# revA.net
KiCad netlist of a schematic drawn in EAGLE
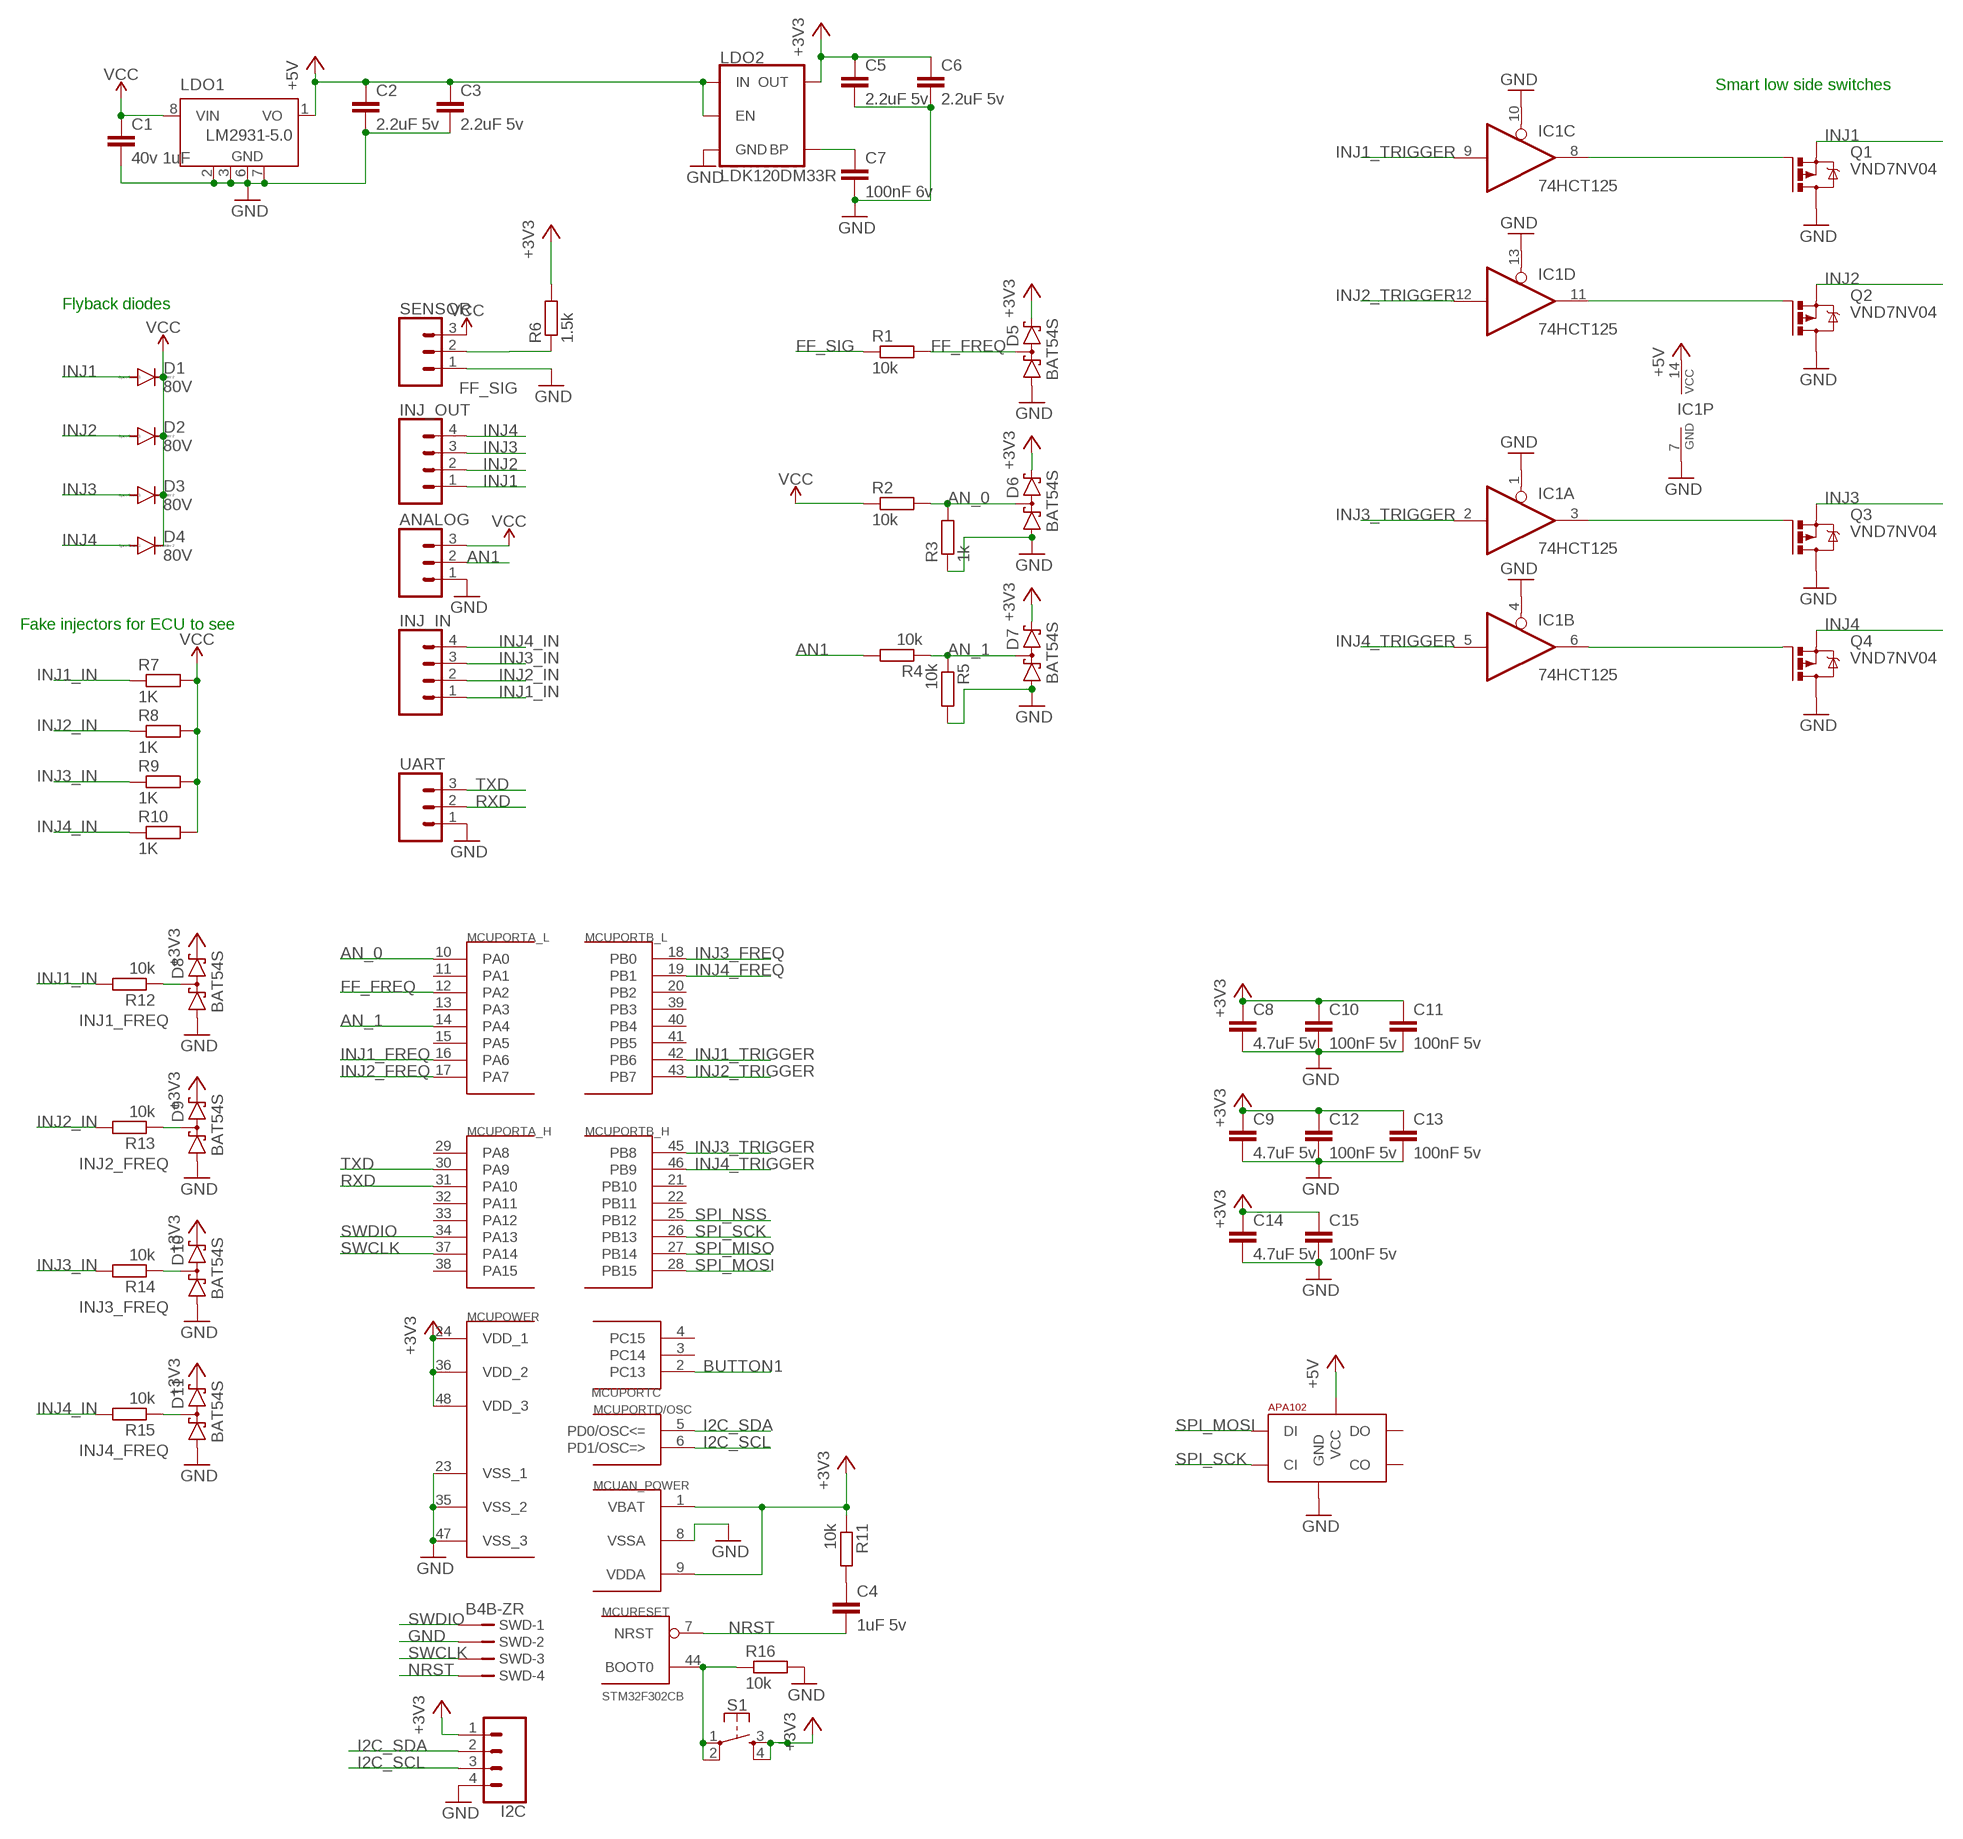
[diagram p0: schematic, sheet 1]

(export (version "E")
  (design (tool "Eeschema 10.0.6"))
  (components
    (comp (ref "ANALOG")
      (value "CONN_03POLAR_LOCK")
      (footprint "eagle-import:MOLEX-1X3_LOCK")
      (libsource (lib "eagle-import") (part "CONN_03POLAR_LOCK"))
    )
    (comp (ref "C1")
      (value "40v 1uF")
      (footprint "eagle-import:C0603")
      (libsource (lib "eagle-import") (part "C-EUC0603"))
    )
    (comp (ref "C2")
      (value "2.2uF 5v")
      (footprint "eagle-import:C0603")
      (libsource (lib "eagle-import") (part "C-EUC0603"))
    )
    (comp (ref "C3")
      (value "2.2uF 5v")
      (footprint "eagle-import:C0603")
      (libsource (lib "eagle-import") (part "C-EUC0603"))
    )
    (comp (ref "C4")
      (value "1uF 5v")
      (footprint "eagle-import:C0603")
      (libsource (lib "eagle-import") (part "C-EUC0603"))
    )
    (comp (ref "C5")
      (value "2.2uF 5v")
      (footprint "eagle-import:C0603")
      (libsource (lib "eagle-import") (part "C-EUC0603"))
    )
    (comp (ref "C6")
      (value "2.2uF 5v")
      (footprint "eagle-import:C0603")
      (libsource (lib "eagle-import") (part "C-EUC0603"))
    )
    (comp (ref "C7")
      (value "100nF 6v")
      (footprint "eagle-import:C0603")
      (libsource (lib "eagle-import") (part "C-EUC0603"))
    )
    (comp (ref "C8")
      (value "4.7uF 5v")
      (footprint "eagle-import:C0603")
      (libsource (lib "eagle-import") (part "C-EUC0603"))
    )
    (comp (ref "C9")
      (value "4.7uF 5v")
      (footprint "eagle-import:C0603")
      (libsource (lib "eagle-import") (part "C-EUC0603"))
    )
    (comp (ref "C10")
      (value "100nF 5v")
      (footprint "eagle-import:C0603")
      (libsource (lib "eagle-import") (part "C-EUC0603"))
    )
    (comp (ref "C11")
      (value "100nF 5v")
      (footprint "eagle-import:C0603")
      (libsource (lib "eagle-import") (part "C-EUC0603"))
    )
    (comp (ref "C12")
      (value "100nF 5v")
      (footprint "eagle-import:C0603")
      (libsource (lib "eagle-import") (part "C-EUC0603"))
    )
    (comp (ref "C13")
      (value "100nF 5v")
      (footprint "eagle-import:C0603")
      (libsource (lib "eagle-import") (part "C-EUC0603"))
    )
    (comp (ref "C14")
      (value "4.7uF 5v")
      (footprint "eagle-import:C0603")
      (libsource (lib "eagle-import") (part "C-EUC0603"))
    )
    (comp (ref "C15")
      (value "100nF 5v")
      (footprint "eagle-import:C0603")
      (libsource (lib "eagle-import") (part "C-EUC0603"))
    )
    (comp (ref "D1")
      (value "80V")
      (footprint "eagle-import:SMB")
      (libsource (lib "eagle-import") (part "DIODE-SMB"))
    )
    (comp (ref "D2")
      (value "80V")
      (footprint "eagle-import:SMB")
      (libsource (lib "eagle-import") (part "DIODE-SMB"))
    )
    (comp (ref "D3")
      (value "80V")
      (footprint "eagle-import:SMB")
      (libsource (lib "eagle-import") (part "DIODE-SMB"))
    )
    (comp (ref "D4")
      (value "80V")
      (footprint "eagle-import:SMB")
      (libsource (lib "eagle-import") (part "DIODE-SMB"))
    )
    (comp (ref "D5")
      (value "BAT54S")
      (footprint "eagle-import:SOT23")
      (libsource (lib "eagle-import") (part "BAT54S"))
    )
    (comp (ref "D6")
      (value "BAT54S")
      (footprint "eagle-import:SOT23")
      (libsource (lib "eagle-import") (part "BAT54S"))
    )
    (comp (ref "D7")
      (value "BAT54S")
      (footprint "eagle-import:SOT23")
      (libsource (lib "eagle-import") (part "BAT54S"))
    )
    (comp (ref "D8")
      (value "BAT54S")
      (footprint "eagle-import:SOT23")
      (libsource (lib "eagle-import") (part "BAT54S"))
    )
    (comp (ref "D9")
      (value "BAT54S")
      (footprint "eagle-import:SOT23")
      (libsource (lib "eagle-import") (part "BAT54S"))
    )
    (comp (ref "D10")
      (value "BAT54S")
      (footprint "eagle-import:SOT23")
      (libsource (lib "eagle-import") (part "BAT54S"))
    )
    (comp (ref "D11")
      (value "BAT54S")
      (footprint "eagle-import:SOT23")
      (libsource (lib "eagle-import") (part "BAT54S"))
    )
    (comp (ref "I2C")
      (value "CONN_04POLAR_LOCK")
      (footprint "eagle-import:MOLEX-1X4_LOCK")
      (libsource (lib "eagle-import") (part "CONN_04POLAR_LOCK"))
    )
    (comp (ref "IC1")
      (value "74HCT125")
      (footprint "eagle-import:TSSOP14")
      (libsource (lib "eagle-import") (part "74125PWABT"))
    )
    (comp (ref "INJ_IN")
      (value "CONN_04POLAR_LOCK")
      (footprint "eagle-import:MOLEX-1X4_LOCK")
      (libsource (lib "eagle-import") (part "CONN_04POLAR_LOCK"))
    )
    (comp (ref "INJ_OUT")
      (value "CONN_04POLAR_LOCK")
      (footprint "eagle-import:MOLEX-1X4_LOCK")
      (libsource (lib "eagle-import") (part "CONN_04POLAR_LOCK"))
    )
    (comp (ref "LDO1")
      (value "LM2931-5.0")
      (footprint "eagle-import:SO08")
      (fields (field (name "MF") "NATIONAL SEMICONDUCTOR") (field (name "MPN") "LM2936M-5.0/NOPB"))
      (libsource (lib "eagle-import") (part "LM2936M?-5.0"))
    )
    (comp (ref "LDO2")
      (value "LDK120DM33R")
      (footprint "eagle-import:SOT23-5")
      (libsource (lib "eagle-import") (part "V_REG_MIC52053.3V"))
    )
    (comp (ref "LED")
      (value "APA1025050")
      (footprint "eagle-import:APA102_5050")
      (libsource (lib "eagle-import") (part "APA1025050"))
    )
    (comp (ref "MCU")
      (value "STM32F302CB")
      (footprint "eagle-import:LQFP48_2")
      (libsource (lib "eagle-import") (part "STM32F10XCXT6"))
    )
    (comp (ref "Q1")
      (value "VND7NV04")
      (footprint "eagle-import:D-PAK_TO252AA")
      (libsource (lib "eagle-import") (part "IRF?5305R"))
    )
    (comp (ref "Q2")
      (value "VND7NV04")
      (footprint "eagle-import:D-PAK_TO252AA")
      (libsource (lib "eagle-import") (part "IRF?5305R"))
    )
    (comp (ref "Q3")
      (value "VND7NV04")
      (footprint "eagle-import:D-PAK_TO252AA")
      (libsource (lib "eagle-import") (part "IRF?5305R"))
    )
    (comp (ref "Q4")
      (value "VND7NV04")
      (footprint "eagle-import:D-PAK_TO252AA")
      (libsource (lib "eagle-import") (part "IRF?5305R"))
    )
    (comp (ref "R1")
      (value "10k")
      (footprint "eagle-import:R0603")
      (libsource (lib "eagle-import") (part "R-EU_R0603"))
    )
    (comp (ref "R2")
      (value "10k")
      (footprint "eagle-import:R0603")
      (libsource (lib "eagle-import") (part "R-EU_R0603"))
    )
    (comp (ref "R3")
      (value "1k")
      (footprint "eagle-import:R0603")
      (libsource (lib "eagle-import") (part "R-EU_R0603"))
    )
    (comp (ref "R4")
      (value "10k")
      (footprint "eagle-import:R0603")
      (libsource (lib "eagle-import") (part "R-EU_R0603"))
    )
    (comp (ref "R5")
      (value "10k")
      (footprint "eagle-import:R0603")
      (libsource (lib "eagle-import") (part "R-EU_R0603"))
    )
    (comp (ref "R6")
      (value "1.5k")
      (footprint "eagle-import:R0603")
      (libsource (lib "eagle-import") (part "R-EU_R0603"))
    )
    (comp (ref "R7")
      (value "1K")
      (footprint "eagle-import:0414_15")
      (libsource (lib "eagle-import") (part "R-EU_0414/15"))
    )
    (comp (ref "R8")
      (value "1K")
      (footprint "eagle-import:0414_15")
      (libsource (lib "eagle-import") (part "R-EU_0414/15"))
    )
    (comp (ref "R9")
      (value "1K")
      (footprint "eagle-import:0414_15")
      (libsource (lib "eagle-import") (part "R-EU_0414/15"))
    )
    (comp (ref "R10")
      (value "1K")
      (footprint "eagle-import:0414_15")
      (libsource (lib "eagle-import") (part "R-EU_0414/15"))
    )
    (comp (ref "R11")
      (value "10k")
      (footprint "eagle-import:R0603")
      (libsource (lib "eagle-import") (part "R-EU_R0603"))
    )
    (comp (ref "R12")
      (value "10k")
      (footprint "eagle-import:R0603")
      (libsource (lib "eagle-import") (part "R-EU_R0603"))
    )
    (comp (ref "R13")
      (value "10k")
      (footprint "eagle-import:R0603")
      (libsource (lib "eagle-import") (part "R-EU_R0603"))
    )
    (comp (ref "R14")
      (value "10k")
      (footprint "eagle-import:R0603")
      (libsource (lib "eagle-import") (part "R-EU_R0603"))
    )
    (comp (ref "R15")
      (value "10k")
      (footprint "eagle-import:R0603")
      (libsource (lib "eagle-import") (part "R-EU_R0603"))
    )
    (comp (ref "R16")
      (value "10k")
      (footprint "eagle-import:R0603")
      (libsource (lib "eagle-import") (part "R-EU_R0603"))
    )
    (comp (ref "S1")
      (value "MOMENTARY-SWITCH-SPST-2-SMD-5.2MM")
      (footprint "eagle-import:TACTILE_SWITCH_SMD_5.2MM")
      (libsource (lib "eagle-import") (part "MOMENTARY-SWITCH-SPST-2-SMD-5.2MM"))
    )
    (comp (ref "SENSOR")
      (value "CONN_03POLAR_LOCK")
      (footprint "eagle-import:MOLEX-1X3_LOCK")
      (libsource (lib "eagle-import") (part "CONN_03POLAR_LOCK"))
    )
    (comp (ref "SWD")
      (value "B4B-ZR")
      (footprint "eagle-import:B4B-ZR")
      (fields (field (name "MF") "FARNELL") (field (name "MPN") "B4B-ZR(LF)(SN)"))
      (libsource (lib "eagle-import") (part "?4B-ZRB"))
    )
    (comp (ref "UART")
      (value "CONN_03POLAR_LOCK")
      (footprint "eagle-import:MOLEX-1X3_LOCK")
      (libsource (lib "eagle-import") (part "CONN_03POLAR_LOCK"))
    )
  )
  (nets
    (net (code "1") (name "+3V3") (class "Default")
      (node (ref "C10") (pin "1") (pinfunction "1_1") (pintype "passive"))
      (node (ref "C11") (pin "1") (pinfunction "1_1") (pintype "passive"))
      (node (ref "C12") (pin "1") (pinfunction "1_1") (pintype "passive"))
      (node (ref "C13") (pin "1") (pinfunction "1_1") (pintype "passive"))
      (node (ref "C14") (pin "1") (pinfunction "1_1") (pintype "passive"))
      (node (ref "C15") (pin "1") (pinfunction "1_1") (pintype "passive"))
      (node (ref "C5") (pin "1") (pinfunction "1_1") (pintype "passive"))
      (node (ref "C6") (pin "1") (pinfunction "1_1") (pintype "passive"))
      (node (ref "C8") (pin "1") (pinfunction "1_1") (pintype "passive"))
      (node (ref "C9") (pin "1") (pinfunction "1_1") (pintype "passive"))
      (node (ref "D10") (pin "2") (pinfunction "C2_2") (pintype "passive"))
      (node (ref "D11") (pin "2") (pinfunction "C2_2") (pintype "passive"))
      (node (ref "D5") (pin "2") (pinfunction "C2_2") (pintype "passive"))
      (node (ref "D6") (pin "2") (pinfunction "C2_2") (pintype "passive"))
      (node (ref "D7") (pin "2") (pinfunction "C2_2") (pintype "passive"))
      (node (ref "D8") (pin "2") (pinfunction "C2_2") (pintype "passive"))
      (node (ref "D9") (pin "2") (pinfunction "C2_2") (pintype "passive"))
      (node (ref "I2C") (pin "1") (pinfunction "1_1") (pintype "passive"))
      (node (ref "LDO2") (pin "5") (pinfunction "OUT_5") (pintype "passive"))
      (node (ref "MCU") (pin "1") (pinfunction "VBAT_1") (pintype "power_in"))
      (node (ref "MCU") (pin "24") (pinfunction "VDD_1_24") (pintype "power_in"))
      (node (ref "MCU") (pin "36") (pinfunction "VDD_2_36") (pintype "power_in"))
      (node (ref "MCU") (pin "48") (pinfunction "VDD_3_48") (pintype "power_in"))
      (node (ref "MCU") (pin "9") (pinfunction "VDDA_9") (pintype "power_in"))
      (node (ref "R11") (pin "1") (pinfunction "1_1") (pintype "passive"))
      (node (ref "R6") (pin "2") (pinfunction "2_2") (pintype "passive"))
      (node (ref "S1") (pin "3") (pinfunction "3_3") (pintype "passive"))
      (node (ref "S1") (pin "4") (pinfunction "4_4") (pintype "passive"))
    )
    (net (code "2") (name "+5V") (class "Default")
      (node (ref "C2") (pin "1") (pinfunction "1_1") (pintype "passive"))
      (node (ref "C3") (pin "1") (pinfunction "1_1") (pintype "passive"))
      (node (ref "IC1") (pin "14") (pinfunction "VCC_14") (pintype "power_in"))
      (node (ref "LDO1") (pin "1") (pinfunction "VO_1") (pintype "passive"))
      (node (ref "LDO2") (pin "1") (pinfunction "IN_1") (pintype "input"))
      (node (ref "LDO2") (pin "3") (pinfunction "EN_3") (pintype "input"))
      (node (ref "LED") (pin "1") (pinfunction "VCC_1") (pintype "bidirectional"))
    )
    (net (code "3") (name "/AN1") (class "Default")
      (node (ref "ANALOG") (pin "2") (pinfunction "2_2") (pintype "passive"))
      (node (ref "R4") (pin "2") (pinfunction "2_2") (pintype "passive"))
    )
    (net (code "4") (name "/AN_0") (class "Default")
      (node (ref "D6") (pin "3") (pinfunction "C1A2_3") (pintype "passive"))
      (node (ref "MCU") (pin "10") (pinfunction "PA0_10") (pintype "bidirectional"))
      (node (ref "R2") (pin "2") (pinfunction "2_2") (pintype "passive"))
      (node (ref "R3") (pin "2") (pinfunction "2_2") (pintype "passive"))
    )
    (net (code "5") (name "/AN_1") (class "Default")
      (node (ref "D7") (pin "3") (pinfunction "C1A2_3") (pintype "passive"))
      (node (ref "MCU") (pin "14") (pinfunction "PA4_14") (pintype "bidirectional"))
      (node (ref "R4") (pin "1") (pinfunction "1_1") (pintype "passive"))
      (node (ref "R5") (pin "1") (pinfunction "1_1") (pintype "passive"))
    )
    (net (code "6") (name "/BUTTON1") (class "Default")
      (node (ref "MCU") (pin "2") (pinfunction "PC13_2") (pintype "bidirectional"))
    )
    (net (code "7") (name "/FF_FREQ") (class "Default")
      (node (ref "D5") (pin "3") (pinfunction "C1A2_3") (pintype "passive"))
      (node (ref "MCU") (pin "12") (pinfunction "PA2_12") (pintype "bidirectional"))
      (node (ref "R1") (pin "2") (pinfunction "2_2") (pintype "passive"))
    )
    (net (code "8") (name "/FF_SIG") (class "Default")
      (node (ref "R1") (pin "1") (pinfunction "1_1") (pintype "passive"))
      (node (ref "R6") (pin "1") (pinfunction "1_1") (pintype "passive"))
      (node (ref "SENSOR") (pin "2") (pinfunction "2_2") (pintype "passive"))
    )
    (net (code "9") (name "/I2C_SCL") (class "Default")
      (node (ref "I2C") (pin "3") (pinfunction "3_3") (pintype "passive"))
      (node (ref "MCU") (pin "6") (pinfunction "PD1/OSC=>_6") (pintype "bidirectional"))
    )
    (net (code "10") (name "/I2C_SDA") (class "Default")
      (node (ref "I2C") (pin "2") (pinfunction "2_2") (pintype "passive"))
      (node (ref "MCU") (pin "5") (pinfunction "PD0/OSC<=_5") (pintype "bidirectional"))
    )
    (net (code "11") (name "/INJ1") (class "Default")
      (node (ref "D1") (pin "A") (pinfunction "A_A") (pintype "passive"))
      (node (ref "INJ_OUT") (pin "1") (pinfunction "1_1") (pintype "passive"))
      (node (ref "Q1") (pin "3") (pinfunction "S_3") (pintype "passive"))
    )
    (net (code "12") (name "/INJ1_FREQ") (class "Default")
      (node (ref "D8") (pin "3") (pinfunction "C1A2_3") (pintype "passive"))
      (node (ref "MCU") (pin "16") (pinfunction "PA6_16") (pintype "bidirectional"))
      (node (ref "R12") (pin "1") (pinfunction "1_1") (pintype "passive"))
    )
    (net (code "13") (name "/INJ1_IN") (class "Default")
      (node (ref "INJ_IN") (pin "1") (pinfunction "1_1") (pintype "passive"))
      (node (ref "R12") (pin "2") (pinfunction "2_2") (pintype "passive"))
      (node (ref "R7") (pin "1") (pinfunction "1_1") (pintype "passive"))
    )
    (net (code "14") (name "/INJ1_TRIGGER") (class "Default")
      (node (ref "IC1") (pin "9") (pinfunction "I_9") (pintype "input"))
      (node (ref "MCU") (pin "42") (pinfunction "PB6_42") (pintype "bidirectional"))
    )
    (net (code "15") (name "/INJ2") (class "Default")
      (node (ref "D2") (pin "A") (pinfunction "A_A") (pintype "passive"))
      (node (ref "INJ_OUT") (pin "2") (pinfunction "2_2") (pintype "passive"))
      (node (ref "Q2") (pin "3") (pinfunction "S_3") (pintype "passive"))
    )
    (net (code "16") (name "/INJ2_FREQ") (class "Default")
      (node (ref "D9") (pin "3") (pinfunction "C1A2_3") (pintype "passive"))
      (node (ref "MCU") (pin "17") (pinfunction "PA7_17") (pintype "bidirectional"))
      (node (ref "R13") (pin "1") (pinfunction "1_1") (pintype "passive"))
    )
    (net (code "17") (name "/INJ2_IN") (class "Default")
      (node (ref "INJ_IN") (pin "2") (pinfunction "2_2") (pintype "passive"))
      (node (ref "R13") (pin "2") (pinfunction "2_2") (pintype "passive"))
      (node (ref "R8") (pin "1") (pinfunction "1_1") (pintype "passive"))
    )
    (net (code "18") (name "/INJ2_TRIGGER") (class "Default")
      (node (ref "IC1") (pin "12") (pinfunction "I_12") (pintype "input"))
      (node (ref "MCU") (pin "43") (pinfunction "PB7_43") (pintype "bidirectional"))
    )
    (net (code "19") (name "/INJ3") (class "Default")
      (node (ref "D3") (pin "A") (pinfunction "A_A") (pintype "passive"))
      (node (ref "INJ_OUT") (pin "3") (pinfunction "3_3") (pintype "passive"))
      (node (ref "Q3") (pin "3") (pinfunction "S_3") (pintype "passive"))
    )
    (net (code "20") (name "/INJ3_FREQ") (class "Default")
      (node (ref "D10") (pin "3") (pinfunction "C1A2_3") (pintype "passive"))
      (node (ref "MCU") (pin "18") (pinfunction "PB0_18") (pintype "bidirectional"))
      (node (ref "R14") (pin "1") (pinfunction "1_1") (pintype "passive"))
    )
    (net (code "21") (name "/INJ3_IN") (class "Default")
      (node (ref "INJ_IN") (pin "3") (pinfunction "3_3") (pintype "passive"))
      (node (ref "R14") (pin "2") (pinfunction "2_2") (pintype "passive"))
      (node (ref "R9") (pin "1") (pinfunction "1_1") (pintype "passive"))
    )
    (net (code "22") (name "/INJ3_TRIGGER") (class "Default")
      (node (ref "IC1") (pin "2") (pinfunction "I_2") (pintype "input"))
      (node (ref "MCU") (pin "45") (pinfunction "PB8_45") (pintype "bidirectional"))
    )
    (net (code "23") (name "/INJ4") (class "Default")
      (node (ref "D4") (pin "A") (pinfunction "A_A") (pintype "passive"))
      (node (ref "INJ_OUT") (pin "4") (pinfunction "4_4") (pintype "passive"))
      (node (ref "Q4") (pin "3") (pinfunction "S_3") (pintype "passive"))
    )
    (net (code "24") (name "/INJ4_FREQ") (class "Default")
      (node (ref "D11") (pin "3") (pinfunction "C1A2_3") (pintype "passive"))
      (node (ref "MCU") (pin "19") (pinfunction "PB1_19") (pintype "bidirectional"))
      (node (ref "R15") (pin "1") (pinfunction "1_1") (pintype "passive"))
    )
    (net (code "25") (name "/INJ4_IN") (class "Default")
      (node (ref "INJ_IN") (pin "4") (pinfunction "4_4") (pintype "passive"))
      (node (ref "R10") (pin "1") (pinfunction "1_1") (pintype "passive"))
      (node (ref "R15") (pin "2") (pinfunction "2_2") (pintype "passive"))
    )
    (net (code "26") (name "/INJ4_TRIGGER") (class "Default")
      (node (ref "IC1") (pin "5") (pinfunction "I_5") (pintype "input"))
      (node (ref "MCU") (pin "46") (pinfunction "PB9_46") (pintype "bidirectional"))
    )
    (net (code "27") (name "/NRST") (class "Default")
      (node (ref "C4") (pin "2") (pinfunction "2_2") (pintype "passive"))
      (node (ref "MCU") (pin "7") (pinfunction "NRST_7") (pintype "input"))
      (node (ref "SWD") (pin "4") (pinfunction "1_4") (pintype "passive"))
    )
    (net (code "28") (name "/RXD") (class "Default")
      (node (ref "MCU") (pin "31") (pinfunction "PA10_31") (pintype "bidirectional"))
      (node (ref "UART") (pin "2") (pinfunction "2_2") (pintype "passive"))
    )
    (net (code "29") (name "/SPI_MISO") (class "Default")
      (node (ref "MCU") (pin "27") (pinfunction "PB14_27") (pintype "bidirectional"))
    )
    (net (code "30") (name "/SPI_MOSI") (class "Default")
      (node (ref "LED") (pin "4") (pinfunction "DI_4") (pintype "bidirectional"))
      (node (ref "MCU") (pin "28") (pinfunction "PB15_28") (pintype "bidirectional"))
    )
    (net (code "31") (name "/SPI_NSS") (class "Default")
      (node (ref "MCU") (pin "25") (pinfunction "PB12_25") (pintype "bidirectional"))
    )
    (net (code "32") (name "/SPI_SCK") (class "Default")
      (node (ref "LED") (pin "5") (pinfunction "CI_5") (pintype "bidirectional"))
      (node (ref "MCU") (pin "26") (pinfunction "PB13_26") (pintype "bidirectional"))
    )
    (net (code "33") (name "/SWCLK") (class "Default")
      (node (ref "MCU") (pin "37") (pinfunction "PA14_37") (pintype "bidirectional"))
      (node (ref "SWD") (pin "3") (pinfunction "1_3") (pintype "passive"))
    )
    (net (code "34") (name "/SWDIO") (class "Default")
      (node (ref "MCU") (pin "34") (pinfunction "PA13_34") (pintype "bidirectional"))
      (node (ref "SWD") (pin "1") (pinfunction "1_1") (pintype "passive"))
    )
    (net (code "35") (name "/TXD") (class "Default")
      (node (ref "MCU") (pin "30") (pinfunction "PA9_30") (pintype "bidirectional"))
      (node (ref "UART") (pin "3") (pinfunction "3_3") (pintype "passive"))
    )
    (net (code "36") (name "GND") (class "Default")
      (node (ref "ANALOG") (pin "1") (pinfunction "1_1") (pintype "passive"))
      (node (ref "C1") (pin "2") (pinfunction "2_2") (pintype "passive"))
      (node (ref "C10") (pin "2") (pinfunction "2_2") (pintype "passive"))
      (node (ref "C11") (pin "2") (pinfunction "2_2") (pintype "passive"))
      (node (ref "C12") (pin "2") (pinfunction "2_2") (pintype "passive"))
      (node (ref "C13") (pin "2") (pinfunction "2_2") (pintype "passive"))
      (node (ref "C14") (pin "2") (pinfunction "2_2") (pintype "passive"))
      (node (ref "C15") (pin "2") (pinfunction "2_2") (pintype "passive"))
      (node (ref "C2") (pin "2") (pinfunction "2_2") (pintype "passive"))
      (node (ref "C3") (pin "2") (pinfunction "2_2") (pintype "passive"))
      (node (ref "C5") (pin "2") (pinfunction "2_2") (pintype "passive"))
      (node (ref "C6") (pin "2") (pinfunction "2_2") (pintype "passive"))
      (node (ref "C7") (pin "2") (pinfunction "2_2") (pintype "passive"))
      (node (ref "C8") (pin "2") (pinfunction "2_2") (pintype "passive"))
      (node (ref "C9") (pin "2") (pinfunction "2_2") (pintype "passive"))
      (node (ref "D10") (pin "1") (pinfunction "A1_1") (pintype "passive"))
      (node (ref "D11") (pin "1") (pinfunction "A1_1") (pintype "passive"))
      (node (ref "D5") (pin "1") (pinfunction "A1_1") (pintype "passive"))
      (node (ref "D6") (pin "1") (pinfunction "A1_1") (pintype "passive"))
      (node (ref "D7") (pin "1") (pinfunction "A1_1") (pintype "passive"))
      (node (ref "D8") (pin "1") (pinfunction "A1_1") (pintype "passive"))
      (node (ref "D9") (pin "1") (pinfunction "A1_1") (pintype "passive"))
      (node (ref "I2C") (pin "4") (pinfunction "4_4") (pintype "passive"))
      (node (ref "IC1") (pin "1") (pinfunction "OE_1") (pintype "input"))
      (node (ref "IC1") (pin "10") (pinfunction "OE_10") (pintype "input"))
      (node (ref "IC1") (pin "13") (pinfunction "OE_13") (pintype "input"))
      (node (ref "IC1") (pin "4") (pinfunction "OE_4") (pintype "input"))
      (node (ref "IC1") (pin "7") (pinfunction "GND_7") (pintype "power_in"))
      (node (ref "LDO1") (pin "2") (pinfunction "GND_2") (pintype "passive"))
      (node (ref "LDO1") (pin "3") (pinfunction "GND_3") (pintype "passive"))
      (node (ref "LDO1") (pin "6") (pinfunction "GND_6") (pintype "passive"))
      (node (ref "LDO1") (pin "7") (pinfunction "GND_7") (pintype "passive"))
      (node (ref "LDO2") (pin "2") (pinfunction "GND_2") (pintype "input"))
      (node (ref "LED") (pin "6") (pinfunction "GND_6") (pintype "bidirectional"))
      (node (ref "MCU") (pin "23") (pinfunction "VSS_1_23") (pintype "power_in"))
      (node (ref "MCU") (pin "35") (pinfunction "VSS_2_35") (pintype "power_in"))
      (node (ref "MCU") (pin "47") (pinfunction "VSS_3_47") (pintype "power_in"))
      (node (ref "MCU") (pin "8") (pinfunction "VSSA_8") (pintype "power_in"))
      (node (ref "Q1") (pin "4") (pinfunction "D_4") (pintype "passive"))
      (node (ref "Q2") (pin "4") (pinfunction "D_4") (pintype "passive"))
      (node (ref "Q3") (pin "4") (pinfunction "D_4") (pintype "passive"))
      (node (ref "Q4") (pin "4") (pinfunction "D_4") (pintype "passive"))
      (node (ref "R16") (pin "2") (pinfunction "2_2") (pintype "passive"))
      (node (ref "R3") (pin "1") (pinfunction "1_1") (pintype "passive"))
      (node (ref "R5") (pin "2") (pinfunction "2_2") (pintype "passive"))
      (node (ref "SENSOR") (pin "1") (pinfunction "1_1") (pintype "passive"))
      (node (ref "SWD") (pin "2") (pinfunction "1_2") (pintype "passive"))
      (node (ref "UART") (pin "1") (pinfunction "1_1") (pintype "passive"))
    )
    (net (code "37") (name "Net-(C4-Pad1)") (class "Default")
      (node (ref "C4") (pin "1") (pinfunction "1_1") (pintype "passive"))
      (node (ref "R11") (pin "2") (pinfunction "2_2") (pintype "passive"))
    )
    (net (code "38") (name "Net-(IC1A-O)") (class "Default")
      (node (ref "IC1") (pin "3") (pinfunction "O_3") (pintype "tri_state"))
      (node (ref "Q3") (pin "1") (pinfunction "G_1") (pintype "passive"))
    )
    (net (code "39") (name "Net-(IC1B-O)") (class "Default")
      (node (ref "IC1") (pin "6") (pinfunction "O_6") (pintype "tri_state"))
      (node (ref "Q4") (pin "1") (pinfunction "G_1") (pintype "passive"))
    )
    (net (code "40") (name "Net-(IC1C-O)") (class "Default")
      (node (ref "IC1") (pin "8") (pinfunction "O_8") (pintype "tri_state"))
      (node (ref "Q1") (pin "1") (pinfunction "G_1") (pintype "passive"))
    )
    (net (code "41") (name "Net-(IC1D-O)") (class "Default")
      (node (ref "IC1") (pin "11") (pinfunction "O_11") (pintype "tri_state"))
      (node (ref "Q2") (pin "1") (pinfunction "G_1") (pintype "passive"))
    )
    (net (code "42") (name "Net-(LDO2-BP)") (class "Default")
      (node (ref "C7") (pin "1") (pinfunction "1_1") (pintype "passive"))
      (node (ref "LDO2") (pin "4") (pinfunction "BP_4") (pintype "input"))
    )
    (net (code "43") (name "Net-(MCUI-BOOT0)") (class "Default")
      (node (ref "MCU") (pin "44") (pinfunction "BOOT0_44") (pintype "input"))
      (node (ref "R16") (pin "1") (pinfunction "1_1") (pintype "passive"))
      (node (ref "S1") (pin "1") (pinfunction "1_1") (pintype "passive"))
      (node (ref "S1") (pin "2") (pinfunction "2_2") (pintype "passive"))
    )
    (net (code "44") (name "VCC") (class "Default")
      (node (ref "ANALOG") (pin "3") (pinfunction "3_3") (pintype "passive"))
      (node (ref "C1") (pin "1") (pinfunction "1_1") (pintype "passive"))
      (node (ref "D1") (pin "C") (pinfunction "C_C") (pintype "passive"))
      (node (ref "D2") (pin "C") (pinfunction "C_C") (pintype "passive"))
      (node (ref "D3") (pin "C") (pinfunction "C_C") (pintype "passive"))
      (node (ref "D4") (pin "C") (pinfunction "C_C") (pintype "passive"))
      (node (ref "LDO1") (pin "8") (pinfunction "VIN_8") (pintype "input"))
      (node (ref "R10") (pin "2") (pinfunction "2_2") (pintype "passive"))
      (node (ref "R2") (pin "1") (pinfunction "1_1") (pintype "passive"))
      (node (ref "R7") (pin "2") (pinfunction "2_2") (pintype "passive"))
      (node (ref "R8") (pin "2") (pinfunction "2_2") (pintype "passive"))
      (node (ref "R9") (pin "2") (pinfunction "2_2") (pintype "passive"))
      (node (ref "SENSOR") (pin "3") (pinfunction "3_3") (pintype "passive"))
    )
    (net (code "45") (name "unconnected-(LED-CO-Pad2)") (class "Default")
      (node (ref "LED") (pin "2") (pinfunction "CO_2") (pintype "bidirectional"))
    )
    (net (code "46") (name "unconnected-(LED-DO-Pad3)") (class "Default")
      (node (ref "LED") (pin "3") (pinfunction "DO_3") (pintype "bidirectional"))
    )
    (net (code "47") (name "unconnected-(MCUB-PA8-Pad29)") (class "Default")
      (node (ref "MCU") (pin "29") (pinfunction "PA8_29") (pintype "bidirectional"))
    )
    (net (code "48") (name "unconnected-(MCUB-PA11-Pad32)") (class "Default")
      (node (ref "MCU") (pin "32") (pinfunction "PA11_32") (pintype "bidirectional"))
    )
    (net (code "49") (name "unconnected-(MCUB-PA12-Pad33)") (class "Default")
      (node (ref "MCU") (pin "33") (pinfunction "PA12_33") (pintype "bidirectional"))
    )
    (net (code "50") (name "unconnected-(MCUB-PA15-Pad38)") (class "Default")
      (node (ref "MCU") (pin "38") (pinfunction "PA15_38") (pintype "bidirectional"))
    )
    (net (code "51") (name "unconnected-(MCUC-PA1-Pad11)") (class "Default")
      (node (ref "MCU") (pin "11") (pinfunction "PA1_11") (pintype "bidirectional"))
    )
    (net (code "52") (name "unconnected-(MCUC-PA3-Pad13)") (class "Default")
      (node (ref "MCU") (pin "13") (pinfunction "PA3_13") (pintype "bidirectional"))
    )
    (net (code "53") (name "unconnected-(MCUC-PA5-Pad15)") (class "Default")
      (node (ref "MCU") (pin "15") (pinfunction "PA5_15") (pintype "bidirectional"))
    )
    (net (code "54") (name "unconnected-(MCUD-PB10-Pad21)") (class "Default")
      (node (ref "MCU") (pin "21") (pinfunction "PB10_21") (pintype "bidirectional"))
    )
    (net (code "55") (name "unconnected-(MCUD-PB11-Pad22)") (class "Default")
      (node (ref "MCU") (pin "22") (pinfunction "PB11_22") (pintype "bidirectional"))
    )
    (net (code "56") (name "unconnected-(MCUE-PB2-Pad20)") (class "Default")
      (node (ref "MCU") (pin "20") (pinfunction "PB2_20") (pintype "bidirectional"))
    )
    (net (code "57") (name "unconnected-(MCUE-PB3-Pad39)") (class "Default")
      (node (ref "MCU") (pin "39") (pinfunction "PB3_39") (pintype "bidirectional"))
    )
    (net (code "58") (name "unconnected-(MCUE-PB4-Pad40)") (class "Default")
      (node (ref "MCU") (pin "40") (pinfunction "PB4_40") (pintype "bidirectional"))
    )
    (net (code "59") (name "unconnected-(MCUE-PB5-Pad41)") (class "Default")
      (node (ref "MCU") (pin "41") (pinfunction "PB5_41") (pintype "bidirectional"))
    )
    (net (code "60") (name "unconnected-(MCUF-PC14-Pad3)") (class "Default")
      (node (ref "MCU") (pin "3") (pinfunction "PC14_3") (pintype "bidirectional"))
    )
    (net (code "61") (name "unconnected-(MCUF-PC15-Pad4)") (class "Default")
      (node (ref "MCU") (pin "4") (pinfunction "PC15_4") (pintype "bidirectional"))
    )
  )
)
